# Sheet1.net
KiCad netlist of a schematic drawn in Altium Designer
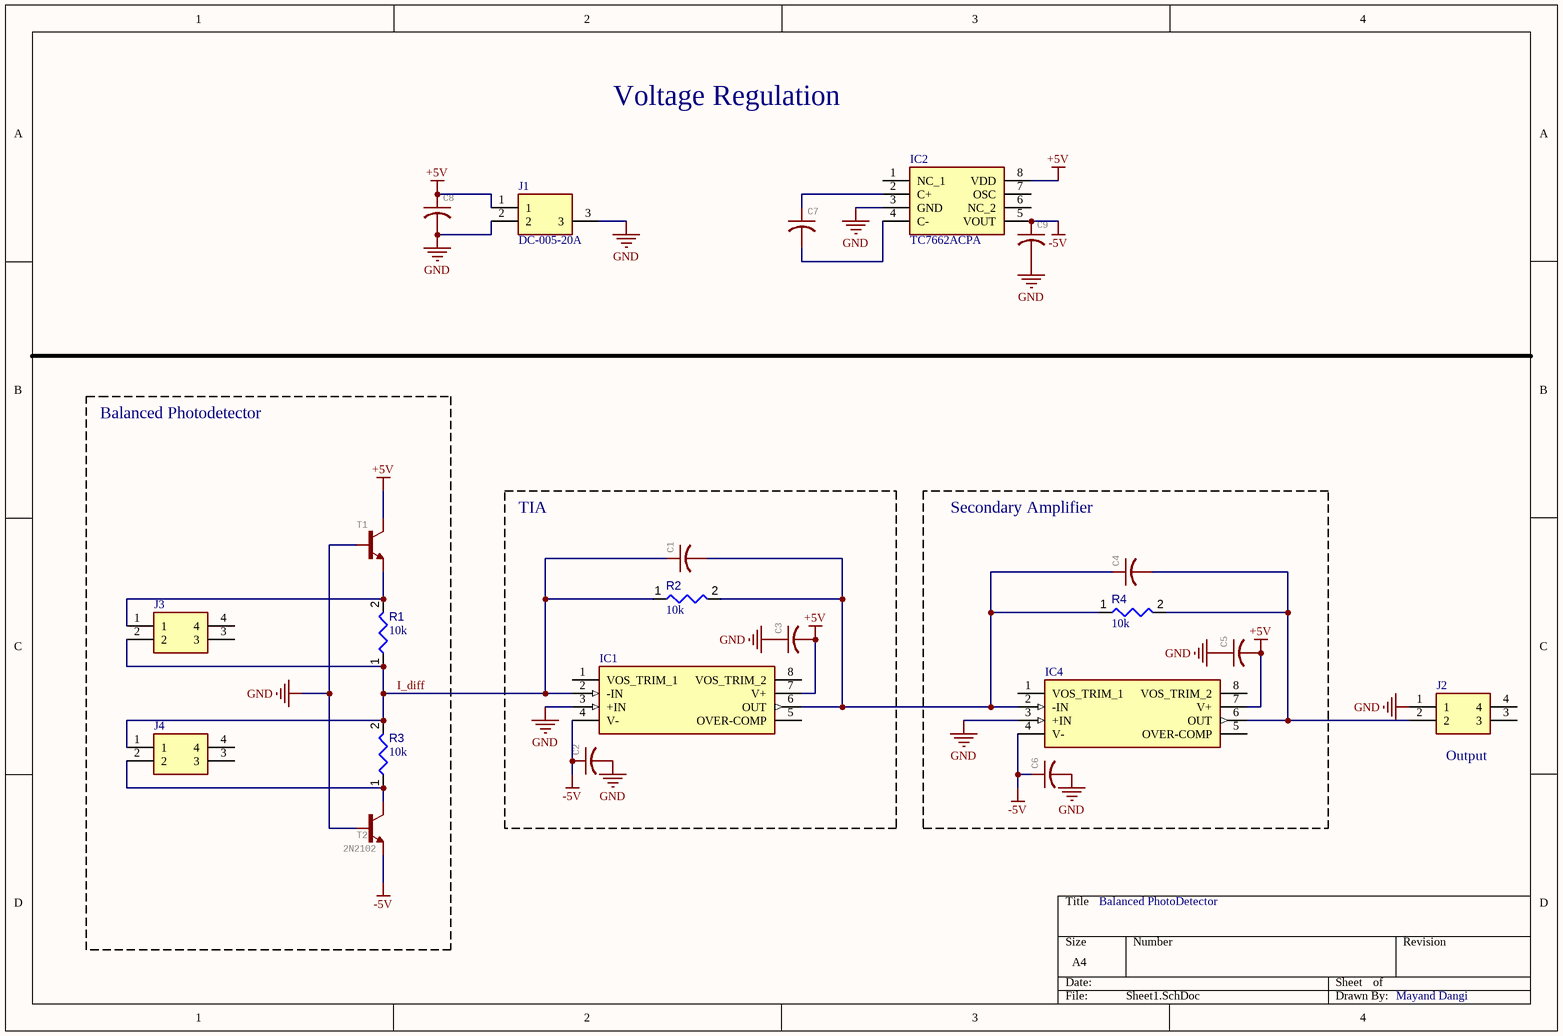
[diagram p0: Sheet1.SchDoc]

(export (version "E")
  (design (tool "Eeschema 10.0.6"))
  (components
    (comp (ref "C1")
      (value "C-US025-030X050")
      (footprint "C025-030X050")
      (description "CAPACITOR, American symbol")
      (libsource (lib "adafruit") (part "C-US025-030X050"))
    )
    (comp (ref "C2")
      (value "C-US025-030X050")
      (footprint "C025-030X050")
      (description "CAPACITOR, American symbol")
      (libsource (lib "adafruit") (part "C-US025-030X050"))
    )
    (comp (ref "C3")
      (value "C-US025-030X050")
      (footprint "C025-030X050")
      (description "CAPACITOR, American symbol")
      (libsource (lib "adafruit") (part "C-US025-030X050"))
    )
    (comp (ref "C4")
      (value "C-US025-030X050")
      (footprint "C025-030X050")
      (description "CAPACITOR, American symbol")
      (libsource (lib "adafruit") (part "C-US025-030X050"))
    )
    (comp (ref "C5")
      (value "C-US025-030X050")
      (footprint "C025-030X050")
      (description "CAPACITOR, American symbol")
      (libsource (lib "adafruit") (part "C-US025-030X050"))
    )
    (comp (ref "C6")
      (value "C-US025-030X050")
      (footprint "C025-030X050")
      (description "CAPACITOR, American symbol")
      (libsource (lib "adafruit") (part "C-US025-030X050"))
    )
    (comp (ref "C7")
      (value "C-US025-030X050")
      (footprint "C025-030X050")
      (description "CAPACITOR, American symbol")
      (libsource (lib "adafruit") (part "C-US025-030X050"))
    )
    (comp (ref "C8")
      (value "C-US025-030X050")
      (footprint "C025-030X050")
      (description "CAPACITOR, American symbol")
      (libsource (lib "adafruit") (part "C-US025-030X050"))
    )
    (comp (ref "C9")
      (value "C-US025-030X050")
      (footprint "C025-030X050")
      (description "CAPACITOR, American symbol")
      (libsource (lib "adafruit") (part "C-US025-030X050"))
    )
    (comp (ref "IC1")
      (value "LT1028ACN8#PBF")
      (footprint "SamacSys:DIP794W53P254L1016H394Q8N")
      (description "Integrated Circuit")
      (libsource (lib "*") (part "LT1028ACN8#PBF"))
    )
    (comp (ref "IC2")
      (value "TC7662ACPA")
      (footprint "SamacSys:DIP762W56P254L950H508Q8N")
      (description "Integrated Circuit")
      (fields (field (name "MOUSER PART NUMBER") "579-TC7662ACPA"))
      (libsource (lib "*") (part "TC7662ACPA"))
    )
    (comp (ref "IC4")
      (value "LT1028ACN8#PBF")
      (footprint "SamacSys:DIP794W53P254L1016H394Q8N")
      (description "Integrated Circuit")
      (libsource (lib "*") (part "LT1028ACN8#PBF"))
    )
    (comp (ref "J1")
      (value "DC-005-20A")
      (footprint "SamacSys:DC00520A")
      (description "Connector")
      (libsource (lib "*") (part "DC-005-20A"))
    )
    (comp (ref "J2")
      (value "1-1337543-0")
      (footprint "SamacSys:1-1337543-0")
      (description "Connector")
      (fields (field (name "MOUSER PART NUMBER") "571-1-1337543-0"))
      (libsource (lib "*") (part "1-1337543-0"))
    )
    (comp (ref "J3")
      (value "1-1337543-0")
      (footprint "SamacSys:1-1337543-0")
      (description "Connector")
      (fields (field (name "MOUSER PART NUMBER") "571-1-1337543-0"))
      (libsource (lib "*") (part "1-1337543-0"))
    )
    (comp (ref "J4")
      (value "1-1337543-0")
      (footprint "SamacSys:1-1337543-0")
      (description "Connector")
      (fields (field (name "MOUSER PART NUMBER") "571-1-1337543-0"))
      (libsource (lib "*") (part "1-1337543-0"))
    )
    (comp (ref "R1")
      (value "10k")
      (footprint "RESA60-630X240")
      (description "Axial Resistor, 10 KOhm, +/- 1%, 0.25 W, -55 to 155 degC, 2-Pin THD, RoHS, Bulk")
      (fields (field (name "TOLERANCE") "1%") (field (name "POWER") "250mW"))
      (libsource (lib "Axlr8r Formula Racing") (part "RES-2"))
    )
    (comp (ref "R2")
      (value "10k")
      (footprint "RESA60-630X240")
      (description "Axial Resistor, 10 KOhm, +/- 1%, 0.25 W, -55 to 155 degC, 2-Pin THD, RoHS, Bulk")
      (fields (field (name "TOLERANCE") "1%") (field (name "POWER") "250mW"))
      (libsource (lib "Axlr8r Formula Racing") (part "RES-2"))
    )
    (comp (ref "R3")
      (value "10k")
      (footprint "RESA60-630X240")
      (description "Axial Resistor, 10 KOhm, +/- 1%, 0.25 W, -55 to 155 degC, 2-Pin THD, RoHS, Bulk")
      (fields (field (name "TOLERANCE") "1%") (field (name "POWER") "250mW"))
      (libsource (lib "Axlr8r Formula Racing") (part "RES-2"))
    )
    (comp (ref "R4")
      (value "10k")
      (footprint "RESA60-630X240")
      (description "Axial Resistor, 10 KOhm, +/- 1%, 0.25 W, -55 to 155 degC, 2-Pin THD, RoHS, Bulk")
      (fields (field (name "TOLERANCE") "1%") (field (name "POWER") "250mW"))
      (libsource (lib "Axlr8r Formula Racing") (part "RES-2"))
    )
    (comp (ref "T1")
      (value "2N2102")
      (footprint "TO5")
      (description "NPN TRANSISTOR")
      (libsource (lib "transistor") (part "2N2102"))
    )
    (comp (ref "T2")
      (value "2N2102")
      (footprint "TO5")
      (description "NPN TRANSISTOR")
      (libsource (lib "transistor") (part "2N2102"))
    )
  )
  (nets
    (net (code "1") (name "+5V") (class "Default")
      (node (ref "C3") (pin "2") (pinfunction "2_2") (pintype "passive"))
      (node (ref "C5") (pin "2") (pinfunction "2_2") (pintype "passive"))
      (node (ref "C8") (pin "1") (pinfunction "1_1") (pintype "passive"))
      (node (ref "IC1") (pin "7") (pinfunction "V+_7") (pintype "passive"))
      (node (ref "IC2") (pin "8") (pinfunction "VDD_8") (pintype "passive"))
      (node (ref "IC4") (pin "7") (pinfunction "V+_7") (pintype "passive"))
      (node (ref "J1") (pin "1") (pinfunction "1_1") (pintype "passive"))
      (node (ref "T1") (pin "3") (pinfunction "C_3") (pintype "passive"))
    )
    (net (code "2") (name "-5V") (class "Default")
      (node (ref "C2") (pin "1") (pinfunction "1_1") (pintype "passive"))
      (node (ref "C6") (pin "1") (pinfunction "1_1") (pintype "passive"))
      (node (ref "C9") (pin "1") (pinfunction "1_1") (pintype "passive"))
      (node (ref "IC1") (pin "4") (pinfunction "V-_4") (pintype "passive"))
      (node (ref "IC2") (pin "5") (pinfunction "VOUT_5") (pintype "passive"))
      (node (ref "IC4") (pin "4") (pinfunction "V-_4") (pintype "passive"))
      (node (ref "T2") (pin "1") (pinfunction "E_1") (pintype "passive"))
    )
    (net (code "3") (name "/I_diff") (class "Default")
      (node (ref "C1") (pin "1") (pinfunction "1_1") (pintype "passive"))
      (node (ref "IC1") (pin "2") (pinfunction "-IN_2") (pintype "input"))
      (node (ref "J3") (pin "2") (pinfunction "2_2") (pintype "passive"))
      (node (ref "J4") (pin "1") (pinfunction "1_1") (pintype "passive"))
      (node (ref "R1") (pin "1") (pinfunction "1_1") (pintype "passive"))
      (node (ref "R2") (pin "1") (pinfunction "1_1") (pintype "passive"))
      (node (ref "R3") (pin "2") (pinfunction "2_2") (pintype "passive"))
    )
    (net (code "4") (name "GND") (class "Default")
      (node (ref "C2") (pin "2") (pinfunction "2_2") (pintype "passive"))
      (node (ref "C3") (pin "1") (pinfunction "1_1") (pintype "passive"))
      (node (ref "C5") (pin "1") (pinfunction "1_1") (pintype "passive"))
      (node (ref "C6") (pin "2") (pinfunction "2_2") (pintype "passive"))
      (node (ref "C8") (pin "2") (pinfunction "2_2") (pintype "passive"))
      (node (ref "C9") (pin "2") (pinfunction "2_2") (pintype "passive"))
      (node (ref "IC1") (pin "3") (pinfunction "+IN_3") (pintype "input"))
      (node (ref "IC2") (pin "3") (pinfunction "GND_3") (pintype "passive"))
      (node (ref "IC4") (pin "3") (pinfunction "+IN_3") (pintype "input"))
      (node (ref "J1") (pin "2") (pinfunction "2_2") (pintype "passive"))
      (node (ref "J1") (pin "3") (pinfunction "3_3") (pintype "passive"))
      (node (ref "J2") (pin "1") (pinfunction "1_1") (pintype "passive"))
      (node (ref "T1") (pin "2") (pinfunction "B_2") (pintype "passive"))
      (node (ref "T2") (pin "2") (pinfunction "B_2") (pintype "passive"))
    )
    (net (code "5") (name "Net-(IC1-OUT)") (class "Default")
      (node (ref "C1") (pin "2") (pinfunction "2_2") (pintype "passive"))
      (node (ref "C4") (pin "1") (pinfunction "1_1") (pintype "passive"))
      (node (ref "IC1") (pin "6") (pinfunction "OUT_6") (pintype "output"))
      (node (ref "IC4") (pin "2") (pinfunction "-IN_2") (pintype "input"))
      (node (ref "R2") (pin "2") (pinfunction "2_2") (pintype "passive"))
      (node (ref "R4") (pin "1") (pinfunction "1_1") (pintype "passive"))
    )
    (net (code "6") (name "Net-(IC2-C+)") (class "Default")
      (node (ref "C7") (pin "1") (pinfunction "1_1") (pintype "passive"))
      (node (ref "IC2") (pin "2") (pinfunction "C+_2") (pintype "passive"))
    )
    (net (code "7") (name "Net-(IC2-C-)") (class "Default")
      (node (ref "C7") (pin "2") (pinfunction "2_2") (pintype "passive"))
      (node (ref "IC2") (pin "4") (pinfunction "C-_4") (pintype "passive"))
    )
    (net (code "8") (name "Net-(IC4-OUT)") (class "Default")
      (node (ref "C4") (pin "2") (pinfunction "2_2") (pintype "passive"))
      (node (ref "IC4") (pin "6") (pinfunction "OUT_6") (pintype "output"))
      (node (ref "J2") (pin "2") (pinfunction "2_2") (pintype "passive"))
      (node (ref "R4") (pin "2") (pinfunction "2_2") (pintype "passive"))
    )
    (net (code "9") (name "Net-(T1-E)") (class "Default")
      (node (ref "J3") (pin "1") (pinfunction "1_1") (pintype "passive"))
      (node (ref "R1") (pin "2") (pinfunction "2_2") (pintype "passive"))
      (node (ref "T1") (pin "1") (pinfunction "E_1") (pintype "passive"))
    )
    (net (code "10") (name "Net-(T2-C)") (class "Default")
      (node (ref "J4") (pin "2") (pinfunction "2_2") (pintype "passive"))
      (node (ref "R3") (pin "1") (pinfunction "1_1") (pintype "passive"))
      (node (ref "T2") (pin "3") (pinfunction "C_3") (pintype "passive"))
    )
    (net (code "11") (name "unconnected-(IC1-OVER-COMP-Pad5)") (class "Default")
      (node (ref "IC1") (pin "5") (pinfunction "OVER-COMP_5") (pintype "passive"))
    )
    (net (code "12") (name "unconnected-(IC1-VOS_TRIM_1-Pad1)") (class "Default")
      (node (ref "IC1") (pin "1") (pinfunction "VOS_TRIM_1_1") (pintype "passive"))
    )
    (net (code "13") (name "unconnected-(IC1-VOS_TRIM_2-Pad8)") (class "Default")
      (node (ref "IC1") (pin "8") (pinfunction "VOS_TRIM_2_8") (pintype "passive"))
    )
    (net (code "14") (name "unconnected-(IC2-NC_1-Pad1)") (class "Default")
      (node (ref "IC2") (pin "1") (pinfunction "NC_1_1") (pintype "passive"))
    )
    (net (code "15") (name "unconnected-(IC2-NC_2-Pad6)") (class "Default")
      (node (ref "IC2") (pin "6") (pinfunction "NC_2_6") (pintype "passive"))
    )
    (net (code "16") (name "unconnected-(IC2-OSC-Pad7)") (class "Default")
      (node (ref "IC2") (pin "7") (pinfunction "OSC_7") (pintype "passive"))
    )
    (net (code "17") (name "unconnected-(IC4-OVER-COMP-Pad5)") (class "Default")
      (node (ref "IC4") (pin "5") (pinfunction "OVER-COMP_5") (pintype "passive"))
    )
    (net (code "18") (name "unconnected-(IC4-VOS_TRIM_1-Pad1)") (class "Default")
      (node (ref "IC4") (pin "1") (pinfunction "VOS_TRIM_1_1") (pintype "passive"))
    )
    (net (code "19") (name "unconnected-(IC4-VOS_TRIM_2-Pad8)") (class "Default")
      (node (ref "IC4") (pin "8") (pinfunction "VOS_TRIM_2_8") (pintype "passive"))
    )
    (net (code "20") (name "unconnected-(J2-Pad3)") (class "Default")
      (node (ref "J2") (pin "3") (pinfunction "3_3") (pintype "passive"))
    )
    (net (code "21") (name "unconnected-(J2-Pad4)") (class "Default")
      (node (ref "J2") (pin "4") (pinfunction "4_4") (pintype "passive"))
    )
    (net (code "22") (name "unconnected-(J3-Pad3)") (class "Default")
      (node (ref "J3") (pin "3") (pinfunction "3_3") (pintype "passive"))
    )
    (net (code "23") (name "unconnected-(J3-Pad4)") (class "Default")
      (node (ref "J3") (pin "4") (pinfunction "4_4") (pintype "passive"))
    )
    (net (code "24") (name "unconnected-(J4-Pad3)") (class "Default")
      (node (ref "J4") (pin "3") (pinfunction "3_3") (pintype "passive"))
    )
    (net (code "25") (name "unconnected-(J4-Pad4)") (class "Default")
      (node (ref "J4") (pin "4") (pinfunction "4_4") (pintype "passive"))
    )
  )
)
